# Right_Ear_Board.net
KiCad netlist of a schematic drawn in EAGLE
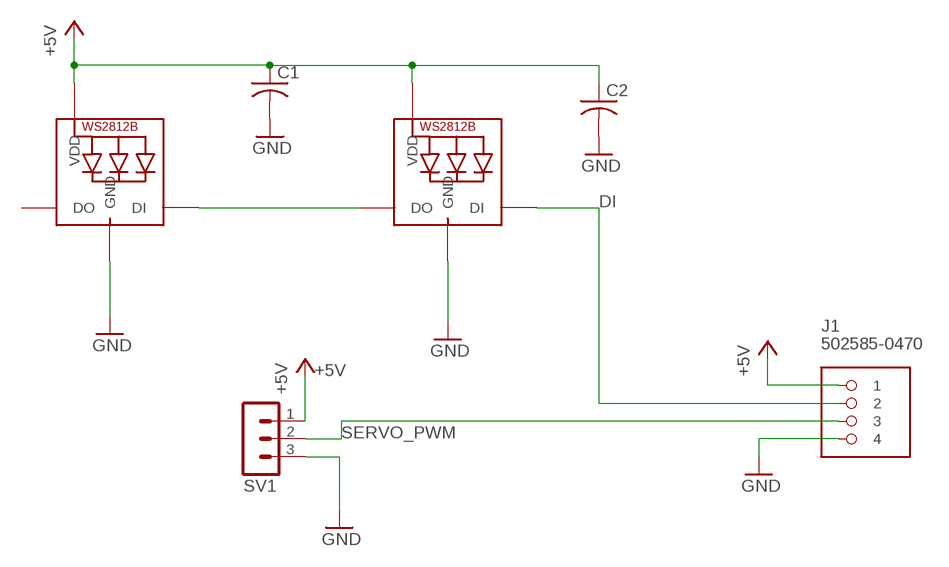
[diagram p0: schematic, sheet 1]

(export (version "E")
  (design (tool "Eeschema 10.0.6"))
  (components
    (comp (ref "C1")
      (value "C-USC0402")
      (footprint "eagle-import:C0402")
      (libsource (lib "eagle-import") (part "C-USC0402"))
    )
    (comp (ref "C2")
      (value "C-USC0402")
      (footprint "eagle-import:C0402")
      (libsource (lib "eagle-import") (part "C-USC0402"))
    )
    (comp (ref "J1")
      (value "502585-0470")
      (footprint "eagle-import:MOLEX-CLIKMATE-4-R_A")
      (libsource (lib "eagle-import") (part "MOLEX_CLICKMATE-4-R/A"))
    )
    (comp (ref "LED1")
      (value "WS2812B5050")
      (footprint "eagle-import:WS2812B")
      (libsource (lib "eagle-import") (part "WS2812B5050"))
    )
    (comp (ref "LED7")
      (value "WS2812B5050")
      (footprint "eagle-import:WS2812B")
      (libsource (lib "eagle-import") (part "WS2812B5050"))
    )
    (comp (ref "SV1")
      (value "MA03-1")
      (footprint "eagle-import:MA03-1")
      (libsource (lib "eagle-import") (part "MA03-1"))
    )
  )
  (nets
    (net (code "1") (name "+5V") (class "Default")
      (node (ref "C1") (pin "1") (pinfunction "1_1") (pintype "passive"))
      (node (ref "C2") (pin "1") (pinfunction "1_1") (pintype "passive"))
      (node (ref "J1") (pin "1") (pinfunction "1_1") (pintype "bidirectional"))
      (node (ref "LED1") (pin "1-VDD") (pinfunction "VDD_1-VDD") (pintype "power_in"))
      (node (ref "LED7") (pin "1-VDD") (pinfunction "VDD_1-VDD") (pintype "power_in"))
      (node (ref "SV1") (pin "1") (pinfunction "1_1") (pintype "passive"))
    )
    (net (code "2") (name "/DI") (class "Default")
      (node (ref "J1") (pin "2") (pinfunction "2_2") (pintype "bidirectional"))
      (node (ref "LED1") (pin "4-DIN") (pinfunction "DI_4-DIN") (pintype "input"))
    )
    (net (code "3") (name "/SERVO_PWM") (class "Default")
      (node (ref "J1") (pin "3") (pinfunction "3_3") (pintype "bidirectional"))
      (node (ref "SV1") (pin "2") (pinfunction "2_2") (pintype "passive"))
    )
    (net (code "4") (name "GND") (class "Default")
      (node (ref "C1") (pin "2") (pinfunction "2_2") (pintype "passive"))
      (node (ref "C2") (pin "2") (pinfunction "2_2") (pintype "passive"))
      (node (ref "J1") (pin "4") (pinfunction "4_4") (pintype "bidirectional"))
      (node (ref "LED1") (pin "3-GND") (pinfunction "GND_3-GND") (pintype "power_in"))
      (node (ref "LED7") (pin "3-GND") (pinfunction "GND_3-GND") (pintype "power_in"))
      (node (ref "SV1") (pin "3") (pinfunction "3_3") (pintype "passive"))
    )
    (net (code "5") (name "Net-(LED1-DO)") (class "Default")
      (node (ref "LED1") (pin "2-DOUT") (pinfunction "DO_2-DOUT") (pintype "output"))
      (node (ref "LED7") (pin "4-DIN") (pinfunction "DI_4-DIN") (pintype "input"))
    )
    (net (code "6") (name "unconnected-(LED7-DO-Pad2-DOUT)") (class "Default")
      (node (ref "LED7") (pin "2-DOUT") (pinfunction "DO_2-DOUT") (pintype "output"))
    )
  )
)
